# IRQF103C8revC.net
KiCad netlist of a schematic drawn in EAGLE
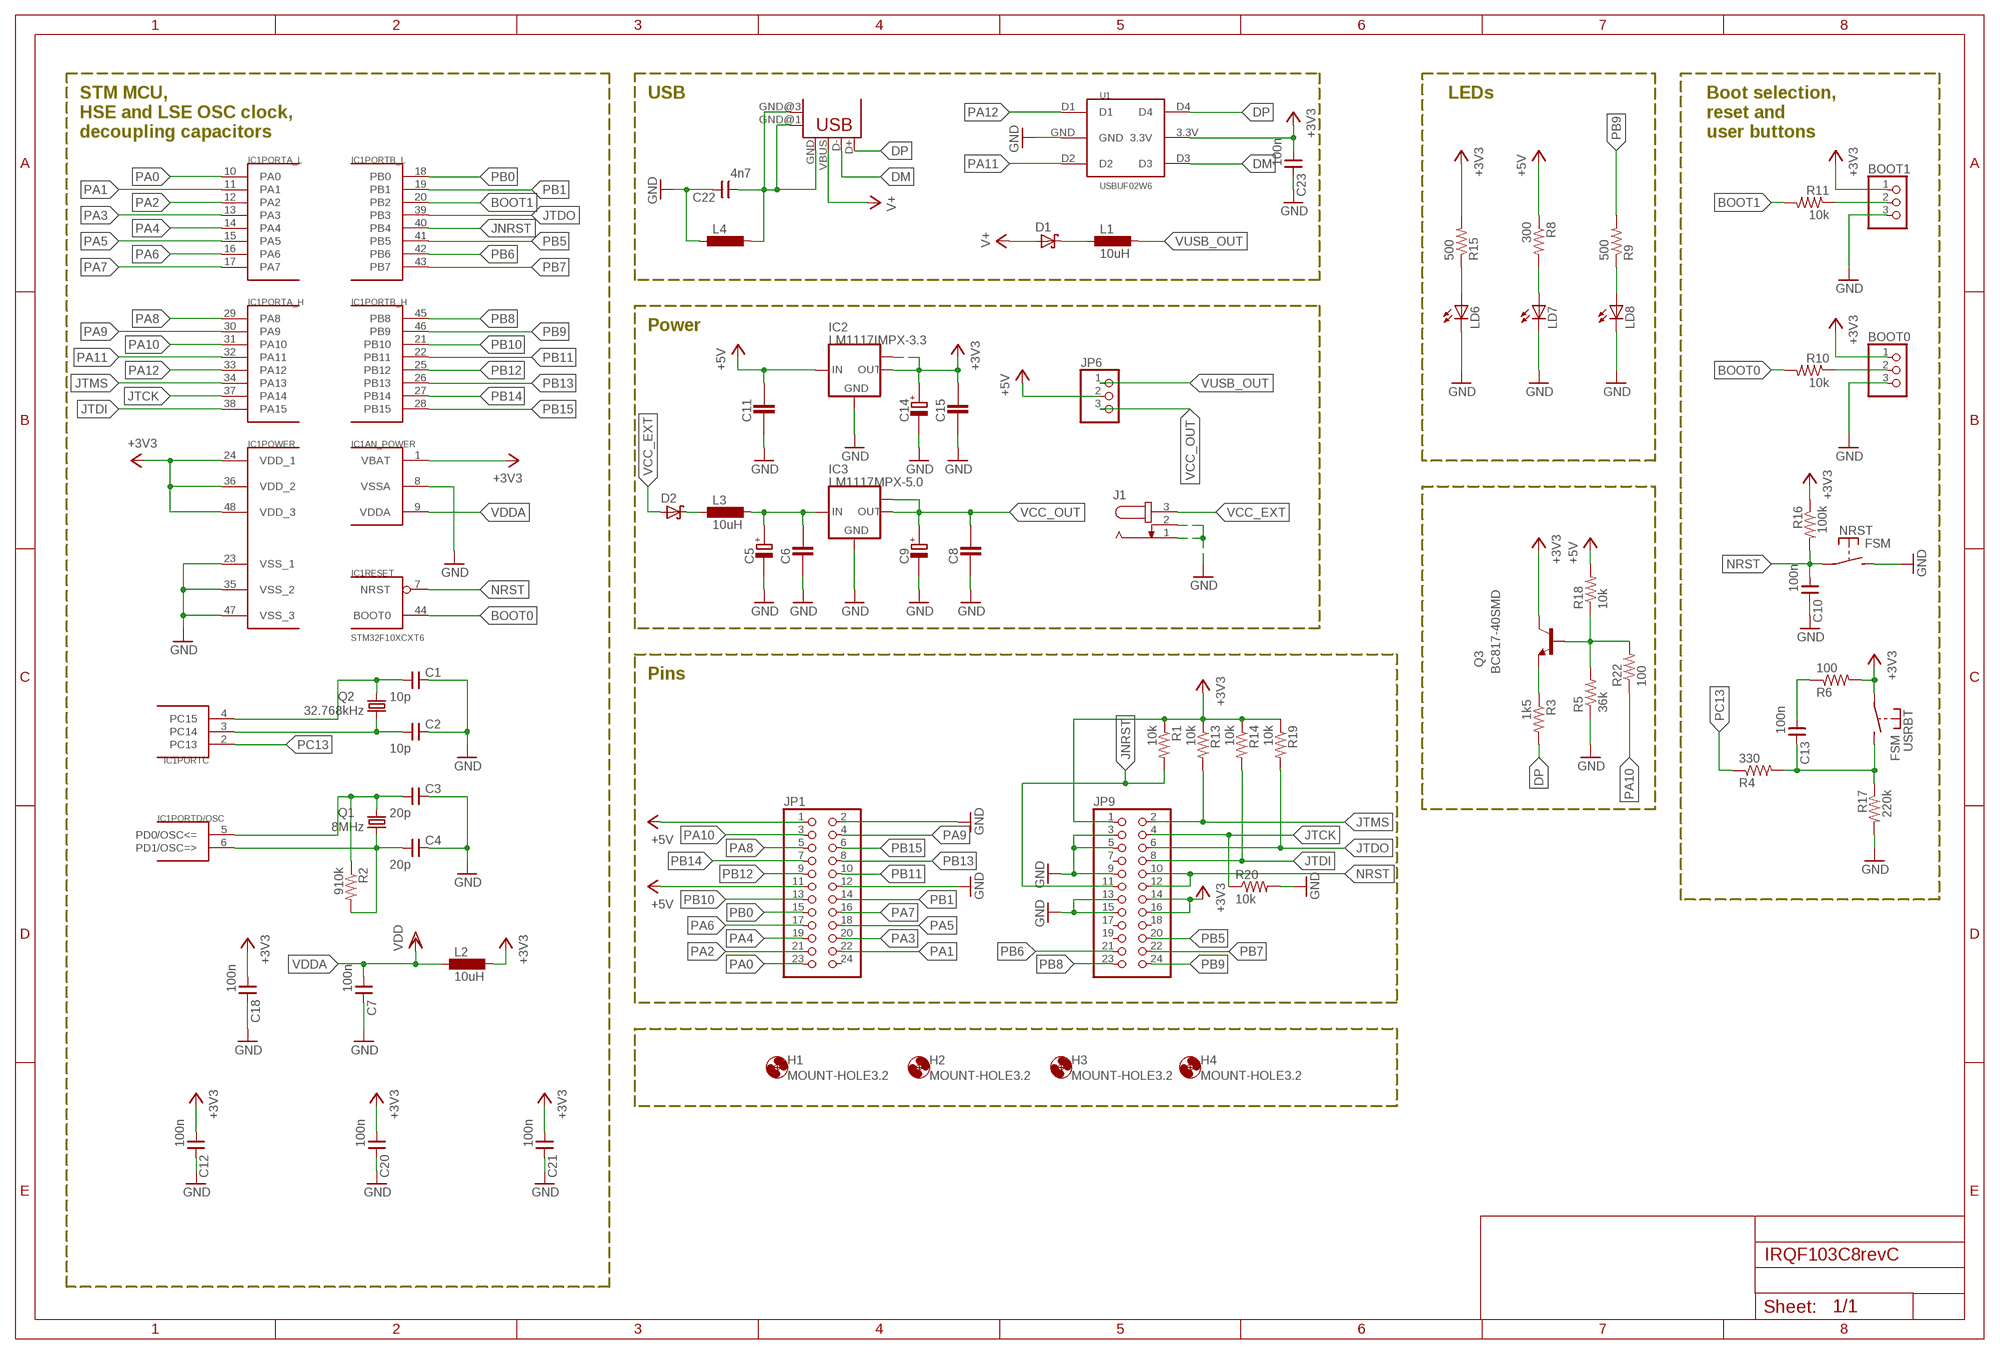
[diagram p0: schematic, sheet 1]

(export (version "E")
  (design (tool "Eeschema 10.0.6"))
  (components
    (comp (ref "BOOT0")
      (value "PINHD-1X3")
      (footprint "eagle-import:1X03")
      (libsource (lib "eagle-import") (part "PINHD-1X3"))
    )
    (comp (ref "BOOT1")
      (value "PINHD-1X3")
      (footprint "eagle-import:1X03")
      (libsource (lib "eagle-import") (part "PINHD-1X3"))
    )
    (comp (ref "C1")
      (value "10p")
      (footprint "eagle-import:0805")
      (libsource (lib "eagle-import") (part "CNP-0805"))
    )
    (comp (ref "C2")
      (value "10p")
      (footprint "eagle-import:0805")
      (libsource (lib "eagle-import") (part "CNP-0805"))
    )
    (comp (ref "C3")
      (value "20p")
      (footprint "eagle-import:0805")
      (libsource (lib "eagle-import") (part "CNP-0805"))
    )
    (comp (ref "C4")
      (value "20p")
      (footprint "eagle-import:0805")
      (libsource (lib "eagle-import") (part "CNP-0805"))
    )
    (comp (ref "C5")
      (value "POLARISED_CASE_B")
      (footprint "eagle-import:CAPAE430X540N")
      (libsource (lib "eagle-import") (part "POLARISED_CASE_B"))
    )
    (comp (ref "C6")
      (value "CAPACITOR_0805")
      (footprint "eagle-import:CAPC2012X145AN")
      (libsource (lib "eagle-import") (part "CAPACITOR_0805"))
    )
    (comp (ref "C7")
      (value "100n")
      (footprint "eagle-import:0805")
      (libsource (lib "eagle-import") (part "CNP-0805"))
    )
    (comp (ref "C8")
      (value "CAPACITOR_0805")
      (footprint "eagle-import:CAPC2012X145AN")
      (libsource (lib "eagle-import") (part "CAPACITOR_0805"))
    )
    (comp (ref "C9")
      (value "POLARISED_CASE_D")
      (footprint "eagle-import:CAPAE660X540N")
      (libsource (lib "eagle-import") (part "POLARISED_CASE_D"))
    )
    (comp (ref "C10")
      (value "100n")
      (footprint "eagle-import:0805")
      (libsource (lib "eagle-import") (part "CNP-0805"))
    )
    (comp (ref "C11")
      (value "CAPACITOR_1206")
      (footprint "eagle-import:CAPC3215X168N")
      (libsource (lib "eagle-import") (part "CAPACITOR_1206"))
    )
    (comp (ref "C12")
      (value "100n")
      (footprint "eagle-import:0805")
      (libsource (lib "eagle-import") (part "CNP-0805"))
    )
    (comp (ref "C13")
      (value "100n")
      (footprint "eagle-import:0805")
      (libsource (lib "eagle-import") (part "CNP-0805"))
    )
    (comp (ref "C14")
      (value "POLARISED_CASE_C")
      (footprint "eagle-import:CAPAE530X540N")
      (libsource (lib "eagle-import") (part "POLARISED_CASE_C"))
    )
    (comp (ref "C15")
      (value "CAPACITOR_0805")
      (footprint "eagle-import:CAPC2012X145AN")
      (libsource (lib "eagle-import") (part "CAPACITOR_0805"))
    )
    (comp (ref "C18")
      (value "100n")
      (footprint "eagle-import:0805")
      (libsource (lib "eagle-import") (part "CNP-0805"))
    )
    (comp (ref "C20")
      (value "100n")
      (footprint "eagle-import:0805")
      (libsource (lib "eagle-import") (part "CNP-0805"))
    )
    (comp (ref "C21")
      (value "100n")
      (footprint "eagle-import:0805")
      (libsource (lib "eagle-import") (part "CNP-0805"))
    )
    (comp (ref "C22")
      (value "4n7")
      (footprint "eagle-import:0805")
      (libsource (lib "eagle-import") (part "CNP-0805"))
    )
    (comp (ref "C23")
      (value "100n")
      (footprint "eagle-import:0805")
      (libsource (lib "eagle-import") (part "CNP-0805"))
    )
    (comp (ref "D1")
      (value "SCHOTTKY_SMA")
      (footprint "eagle-import:DIOM5326X292N")
      (libsource (lib "eagle-import") (part "SCHOTTKY_SMA"))
    )
    (comp (ref "D2")
      (value "SCHOTTKY_SMA")
      (footprint "eagle-import:DIOM5326X292N")
      (libsource (lib "eagle-import") (part "SCHOTTKY_SMA"))
    )
    (comp (ref "H1")
      (value "MOUNT-HOLE3.2")
      (footprint "eagle-import:3,2")
      (libsource (lib "eagle-import") (part "MOUNT-HOLE3.2"))
    )
    (comp (ref "H2")
      (value "MOUNT-HOLE3.2")
      (footprint "eagle-import:3,2")
      (libsource (lib "eagle-import") (part "MOUNT-HOLE3.2"))
    )
    (comp (ref "H3")
      (value "MOUNT-HOLE3.2")
      (footprint "eagle-import:3,2")
      (libsource (lib "eagle-import") (part "MOUNT-HOLE3.2"))
    )
    (comp (ref "H4")
      (value "MOUNT-HOLE3.2")
      (footprint "eagle-import:3,2")
      (libsource (lib "eagle-import") (part "MOUNT-HOLE3.2"))
    )
    (comp (ref "IC1")
      (value "STM32F10XCXT6")
      (footprint "eagle-import:TQFP48")
      (libsource (lib "eagle-import") (part "STM32F10XCXT6"))
    )
    (comp (ref "IC2")
      (value "LM1117IMPX-3.3")
      (footprint "eagle-import:SOT223")
      (libsource (lib "eagle-import") (part "LM1117IMPX-3.3"))
    )
    (comp (ref "IC3")
      (value "LM1117MPX-5.0")
      (footprint "eagle-import:SOT223")
      (libsource (lib "eagle-import") (part "LM1117MPX-5.0"))
    )
    (comp (ref "J1")
      (value "JACK-PLUG1")
      (footprint "eagle-import:SPC4078")
      (libsource (lib "eagle-import") (part "JACK-PLUG1"))
    )
    (comp (ref "JP1")
      (value "PINHD-2X12")
      (footprint "eagle-import:2X12")
      (libsource (lib "eagle-import") (part "PINHD-2X12"))
    )
    (comp (ref "JP6")
      (value "PINHD-1X3")
      (footprint "eagle-import:1X03")
      (libsource (lib "eagle-import") (part "PINHD-1X3"))
    )
    (comp (ref "JP9")
      (value "PINHD-2X12")
      (footprint "eagle-import:2X12")
      (libsource (lib "eagle-import") (part "PINHD-2X12"))
    )
    (comp (ref "L1")
      (value "10uH")
      (footprint "eagle-import:INDC1608X95N")
      (libsource (lib "eagle-import") (part "INDUCTOR_0603"))
    )
    (comp (ref "L2")
      (value "10uH")
      (footprint "eagle-import:INDC1608X95N")
      (libsource (lib "eagle-import") (part "INDUCTOR_0603"))
    )
    (comp (ref "L3")
      (value "10uH")
      (footprint "eagle-import:INDC1608X95N")
      (libsource (lib "eagle-import") (part "INDUCTOR_0603"))
    )
    (comp (ref "L4")
      (value "INDUCTOR_0603")
      (footprint "eagle-import:INDC1608X95N")
      (libsource (lib "eagle-import") (part "INDUCTOR_0603"))
    )
    (comp (ref "LD6")
      (value "LEDCHIPLED_0805")
      (footprint "eagle-import:CHIPLED_0805")
      (libsource (lib "eagle-import") (part "LEDCHIPLED_0805"))
    )
    (comp (ref "LD7")
      (value "LEDCHIPLED_0805")
      (footprint "eagle-import:CHIPLED_0805")
      (libsource (lib "eagle-import") (part "LEDCHIPLED_0805"))
    )
    (comp (ref "LD8")
      (value "LEDCHIPLED_0805")
      (footprint "eagle-import:CHIPLED_0805")
      (libsource (lib "eagle-import") (part "LEDCHIPLED_0805"))
    )
    (comp (ref "NRST")
      (value "FSM")
      (footprint "eagle-import:FSM")
      (libsource (lib "eagle-import") (part "FSM"))
    )
    (comp (ref "Q1")
      (value "8MHz")
      (footprint "eagle-import:HC49_S")
      (libsource (lib "eagle-import") (part "CRYTALHC49S"))
    )
    (comp (ref "Q2")
      (value "32.768kHz")
      (footprint "eagle-import:TC26H")
      (libsource (lib "eagle-import") (part "CRYTALTC26H"))
    )
    (comp (ref "Q3")
      (value "BC817-40SMD")
      (footprint "eagle-import:SOT23-BEC")
      (libsource (lib "eagle-import") (part "BC817SMD-40"))
    )
    (comp (ref "R1")
      (value "10k")
      (footprint "eagle-import:M0805")
      (libsource (lib "eagle-import") (part "R-US_M0805"))
    )
    (comp (ref "R2")
      (value "910k")
      (footprint "eagle-import:M0805")
      (libsource (lib "eagle-import") (part "R-US_M0805"))
    )
    (comp (ref "R3")
      (value "1k5")
      (footprint "eagle-import:M0805")
      (libsource (lib "eagle-import") (part "R-US_M0805"))
    )
    (comp (ref "R4")
      (value "330")
      (footprint "eagle-import:M0805")
      (libsource (lib "eagle-import") (part "R-US_M0805"))
    )
    (comp (ref "R5")
      (value "36k")
      (footprint "eagle-import:M0805")
      (libsource (lib "eagle-import") (part "R-US_M0805"))
    )
    (comp (ref "R6")
      (value "100")
      (footprint "eagle-import:M0805")
      (libsource (lib "eagle-import") (part "R-US_M0805"))
    )
    (comp (ref "R8")
      (value "300")
      (footprint "eagle-import:M0805")
      (libsource (lib "eagle-import") (part "R-US_M0805"))
    )
    (comp (ref "R9")
      (value "500")
      (footprint "eagle-import:M0805")
      (libsource (lib "eagle-import") (part "R-US_M0805"))
    )
    (comp (ref "R10")
      (value "10k")
      (footprint "eagle-import:M0805")
      (libsource (lib "eagle-import") (part "R-US_M0805"))
    )
    (comp (ref "R11")
      (value "10k")
      (footprint "eagle-import:M0805")
      (libsource (lib "eagle-import") (part "R-US_M0805"))
    )
    (comp (ref "R13")
      (value "10k")
      (footprint "eagle-import:M0805")
      (libsource (lib "eagle-import") (part "R-US_M0805"))
    )
    (comp (ref "R14")
      (value "10k")
      (footprint "eagle-import:M0805")
      (libsource (lib "eagle-import") (part "R-US_M0805"))
    )
    (comp (ref "R15")
      (value "500")
      (footprint "eagle-import:M0805")
      (libsource (lib "eagle-import") (part "R-US_M0805"))
    )
    (comp (ref "R16")
      (value "100k")
      (footprint "eagle-import:M0805")
      (libsource (lib "eagle-import") (part "R-US_M0805"))
    )
    (comp (ref "R17")
      (value "220k")
      (footprint "eagle-import:M0805")
      (libsource (lib "eagle-import") (part "R-US_M0805"))
    )
    (comp (ref "R18")
      (value "10k")
      (footprint "eagle-import:M0805")
      (libsource (lib "eagle-import") (part "R-US_M0805"))
    )
    (comp (ref "R19")
      (value "10k")
      (footprint "eagle-import:M0805")
      (libsource (lib "eagle-import") (part "R-US_M0805"))
    )
    (comp (ref "R20")
      (value "10k")
      (footprint "eagle-import:M0805")
      (libsource (lib "eagle-import") (part "R-US_M0805"))
    )
    (comp (ref "R22")
      (value "100")
      (footprint "eagle-import:M0805")
      (libsource (lib "eagle-import") (part "R-US_M0805"))
    )
    (comp (ref "U1")
      (value "USBUF02W6")
      (footprint "eagle-import:SOT23-6L")
      (libsource (lib "eagle-import") (part "USBUF02W6"))
    )
    (comp (ref "USB1")
      (value "USB-MB-S")
      (footprint "eagle-import:USB-MB-S")
      (libsource (lib "eagle-import") (part "USB-MB-S"))
    )
    (comp (ref "USRBT")
      (value "FSM")
      (footprint "eagle-import:FSM")
      (libsource (lib "eagle-import") (part "FSM"))
    )
  )
  (nets
    (net (code "1") (name "+3V3") (class "Default")
      (node (ref "BOOT0") (pin "1") (pinfunction "1_1") (pintype "passive"))
      (node (ref "BOOT1") (pin "1") (pinfunction "1_1") (pintype "passive"))
      (node (ref "C12") (pin "1") (pinfunction "1_1") (pintype "passive"))
      (node (ref "C14") (pin "+") (pinfunction "+_+") (pintype "passive"))
      (node (ref "C15") (pin "2") (pinfunction "2_2") (pintype "passive"))
      (node (ref "C18") (pin "1") (pinfunction "1_1") (pintype "passive"))
      (node (ref "C20") (pin "1") (pinfunction "1_1") (pintype "passive"))
      (node (ref "C21") (pin "1") (pinfunction "1_1") (pintype "passive"))
      (node (ref "C23") (pin "1") (pinfunction "1_1") (pintype "passive"))
      (node (ref "IC1") (pin "1") (pinfunction "VBAT_1") (pintype "power_in"))
      (node (ref "IC1") (pin "24") (pinfunction "VDD_1_24") (pintype "power_in"))
      (node (ref "IC1") (pin "36") (pinfunction "VDD_2_36") (pintype "power_in"))
      (node (ref "IC1") (pin "48") (pinfunction "VDD_3_48") (pintype "power_in"))
      (node (ref "IC2") (pin "2") (pinfunction "OUT_2") (pintype "passive"))
      (node (ref "IC2") (pin "TAB") (pinfunction "OUT1_TAB") (pintype "passive"))
      (node (ref "JP9") (pin "1") (pinfunction "1_1") (pintype "passive"))
      (node (ref "JP9") (pin "14") (pinfunction "14_14") (pintype "passive"))
      (node (ref "JP9") (pin "16") (pinfunction "16_16") (pintype "passive"))
      (node (ref "L2") (pin "2") (pinfunction "2_2") (pintype "passive"))
      (node (ref "Q3") (pin "C") (pinfunction "C_C") (pintype "passive"))
      (node (ref "R1") (pin "1") (pinfunction "1_1") (pintype "passive"))
      (node (ref "R13") (pin "1") (pinfunction "1_1") (pintype "passive"))
      (node (ref "R14") (pin "1") (pinfunction "1_1") (pintype "passive"))
      (node (ref "R15") (pin "2") (pinfunction "2_2") (pintype "passive"))
      (node (ref "R16") (pin "1") (pinfunction "1_1") (pintype "passive"))
      (node (ref "R19") (pin "1") (pinfunction "1_1") (pintype "passive"))
      (node (ref "R6") (pin "2") (pinfunction "2_2") (pintype "passive"))
      (node (ref "U1") (pin "3.3V") (pinfunction "3.3V_3.3V") (pintype "bidirectional"))
      (node (ref "USRBT") (pin "P$1") (pinfunction "P_P$1") (pintype "passive"))
    )
    (net (code "2") (name "+5V") (class "Default")
      (node (ref "C11") (pin "2") (pinfunction "2_2") (pintype "passive"))
      (node (ref "IC2") (pin "3") (pinfunction "IN_3") (pintype "input"))
      (node (ref "JP1") (pin "1") (pinfunction "1_1") (pintype "passive"))
      (node (ref "JP1") (pin "11") (pinfunction "11_11") (pintype "passive"))
      (node (ref "JP6") (pin "2") (pinfunction "2_2") (pintype "passive"))
      (node (ref "R18") (pin "2") (pinfunction "2_2") (pintype "passive"))
      (node (ref "R8") (pin "1") (pinfunction "1_1") (pintype "passive"))
    )
    (net (code "3") (name "BOOT0") (class "Default")
      (node (ref "IC1") (pin "44") (pinfunction "BOOT0_44") (pintype "input"))
      (node (ref "R10") (pin "2") (pinfunction "2_2") (pintype "passive"))
    )
    (net (code "4") (name "BOOT1") (class "Default")
      (node (ref "IC1") (pin "20") (pinfunction "PB2_20") (pintype "bidirectional"))
      (node (ref "R11") (pin "2") (pinfunction "2_2") (pintype "passive"))
    )
    (net (code "5") (name "DM") (class "Default")
      (node (ref "U1") (pin "D3") (pinfunction "D3_D3") (pintype "bidirectional"))
      (node (ref "USB1") (pin "D-") (pinfunction "D-_D-") (pintype "bidirectional"))
    )
    (net (code "6") (name "DP") (class "Default")
      (node (ref "R3") (pin "2") (pinfunction "2_2") (pintype "passive"))
      (node (ref "U1") (pin "D4") (pinfunction "D4_D4") (pintype "bidirectional"))
      (node (ref "USB1") (pin "D+") (pinfunction "D+_D+") (pintype "bidirectional"))
    )
    (net (code "7") (name "GND") (class "Default")
      (node (ref "BOOT0") (pin "3") (pinfunction "3_3") (pintype "passive"))
      (node (ref "BOOT1") (pin "3") (pinfunction "3_3") (pintype "passive"))
      (node (ref "C1") (pin "2") (pinfunction "2_2") (pintype "passive"))
      (node (ref "C10") (pin "2") (pinfunction "2_2") (pintype "passive"))
      (node (ref "C11") (pin "1") (pinfunction "1_1") (pintype "passive"))
      (node (ref "C12") (pin "2") (pinfunction "2_2") (pintype "passive"))
      (node (ref "C14") (pin "-") (pinfunction "-_-") (pintype "passive"))
      (node (ref "C15") (pin "1") (pinfunction "1_1") (pintype "passive"))
      (node (ref "C18") (pin "2") (pinfunction "2_2") (pintype "passive"))
      (node (ref "C2") (pin "2") (pinfunction "2_2") (pintype "passive"))
      (node (ref "C20") (pin "2") (pinfunction "2_2") (pintype "passive"))
      (node (ref "C21") (pin "2") (pinfunction "2_2") (pintype "passive"))
      (node (ref "C22") (pin "2") (pinfunction "2_2") (pintype "passive"))
      (node (ref "C23") (pin "2") (pinfunction "2_2") (pintype "passive"))
      (node (ref "C3") (pin "2") (pinfunction "2_2") (pintype "passive"))
      (node (ref "C4") (pin "2") (pinfunction "2_2") (pintype "passive"))
      (node (ref "C5") (pin "-") (pinfunction "-_-") (pintype "passive"))
      (node (ref "C6") (pin "1") (pinfunction "1_1") (pintype "passive"))
      (node (ref "C7") (pin "2") (pinfunction "2_2") (pintype "passive"))
      (node (ref "C8") (pin "1") (pinfunction "1_1") (pintype "passive"))
      (node (ref "C9") (pin "-") (pinfunction "-_-") (pintype "passive"))
      (node (ref "IC1") (pin "23") (pinfunction "VSS_1_23") (pintype "power_in"))
      (node (ref "IC1") (pin "35") (pinfunction "VSS_2_35") (pintype "power_in"))
      (node (ref "IC1") (pin "47") (pinfunction "VSS_3_47") (pintype "power_in"))
      (node (ref "IC1") (pin "8") (pinfunction "VSSA_8") (pintype "power_in"))
      (node (ref "IC2") (pin "1") (pinfunction "GND_1") (pintype "input"))
      (node (ref "IC3") (pin "1") (pinfunction "GND_1") (pintype "input"))
      (node (ref "J1") (pin "1") (pinfunction "1_1") (pintype "passive"))
      (node (ref "J1") (pin "2") (pinfunction "2_2") (pintype "passive"))
      (node (ref "JP1") (pin "12") (pinfunction "12_12") (pintype "passive"))
      (node (ref "JP1") (pin "2") (pinfunction "2_2") (pintype "passive"))
      (node (ref "JP9") (pin "13") (pinfunction "13_13") (pintype "passive"))
      (node (ref "JP9") (pin "15") (pinfunction "15_15") (pintype "passive"))
      (node (ref "JP9") (pin "3") (pinfunction "3_3") (pintype "passive"))
      (node (ref "JP9") (pin "5") (pinfunction "5_5") (pintype "passive"))
      (node (ref "JP9") (pin "9") (pinfunction "9_9") (pintype "passive"))
      (node (ref "L4") (pin "1") (pinfunction "1_1") (pintype "passive"))
      (node (ref "LD6") (pin "C") (pinfunction "C_C") (pintype "passive"))
      (node (ref "LD7") (pin "C") (pinfunction "C_C") (pintype "passive"))
      (node (ref "LD8") (pin "C") (pinfunction "C_C") (pintype "passive"))
      (node (ref "NRST") (pin "P$2") (pinfunction "S_P$2") (pintype "passive"))
      (node (ref "R17") (pin "2") (pinfunction "2_2") (pintype "passive"))
      (node (ref "R20") (pin "2") (pinfunction "2_2") (pintype "passive"))
      (node (ref "R5") (pin "1") (pinfunction "1_1") (pintype "passive"))
      (node (ref "U1") (pin "GND") (pinfunction "GND_GND") (pintype "bidirectional"))
    )
    (net (code "8") (name "JNRST") (class "Default")
      (node (ref "IC1") (pin "40") (pinfunction "PB4_40") (pintype "bidirectional"))
      (node (ref "JP9") (pin "11") (pinfunction "11_11") (pintype "passive"))
      (node (ref "R1") (pin "2") (pinfunction "2_2") (pintype "passive"))
    )
    (net (code "9") (name "JTCK") (class "Default")
      (node (ref "IC1") (pin "37") (pinfunction "PA14_37") (pintype "bidirectional"))
      (node (ref "JP9") (pin "4") (pinfunction "4_4") (pintype "passive"))
      (node (ref "R20") (pin "1") (pinfunction "1_1") (pintype "passive"))
    )
    (net (code "10") (name "JTDI") (class "Default")
      (node (ref "IC1") (pin "38") (pinfunction "PA15_38") (pintype "bidirectional"))
      (node (ref "JP9") (pin "8") (pinfunction "8_8") (pintype "passive"))
      (node (ref "R14") (pin "2") (pinfunction "2_2") (pintype "passive"))
    )
    (net (code "11") (name "JTDO") (class "Default")
      (node (ref "IC1") (pin "39") (pinfunction "PB3_39") (pintype "bidirectional"))
      (node (ref "JP9") (pin "6") (pinfunction "6_6") (pintype "passive"))
      (node (ref "R19") (pin "2") (pinfunction "2_2") (pintype "passive"))
    )
    (net (code "12") (name "JTMS") (class "Default")
      (node (ref "IC1") (pin "34") (pinfunction "PA13_34") (pintype "bidirectional"))
      (node (ref "JP9") (pin "2") (pinfunction "2_2") (pintype "passive"))
      (node (ref "R13") (pin "2") (pinfunction "2_2") (pintype "passive"))
    )
    (net (code "13") (name "NRST") (class "Default")
      (node (ref "C10") (pin "1") (pinfunction "1_1") (pintype "passive"))
      (node (ref "IC1") (pin "7") (pinfunction "NRST_7") (pintype "input"))
      (node (ref "JP9") (pin "10") (pinfunction "10_10") (pintype "passive"))
      (node (ref "JP9") (pin "12") (pinfunction "12_12") (pintype "passive"))
      (node (ref "NRST") (pin "P$1") (pinfunction "P_P$1") (pintype "passive"))
      (node (ref "R16") (pin "2") (pinfunction "2_2") (pintype "passive"))
    )
    (net (code "14") (name "Net-(BOOT0-Pad2)") (class "Default")
      (node (ref "BOOT0") (pin "2") (pinfunction "2_2") (pintype "passive"))
      (node (ref "R10") (pin "1") (pinfunction "1_1") (pintype "passive"))
    )
    (net (code "15") (name "Net-(BOOT1-Pad2)") (class "Default")
      (node (ref "BOOT1") (pin "2") (pinfunction "2_2") (pintype "passive"))
      (node (ref "R11") (pin "1") (pinfunction "1_1") (pintype "passive"))
    )
    (net (code "16") (name "Net-(C13-Pad1)") (class "Default")
      (node (ref "C13") (pin "1") (pinfunction "1_1") (pintype "passive"))
      (node (ref "R6") (pin "1") (pinfunction "1_1") (pintype "passive"))
    )
    (net (code "17") (name "Net-(C22-Pad1)") (class "Default")
      (node (ref "C22") (pin "1") (pinfunction "1_1") (pintype "passive"))
      (node (ref "L4") (pin "2") (pinfunction "2_2") (pintype "passive"))
      (node (ref "USB1") (pin "GND") (pinfunction "GND_GND") (pintype "bidirectional"))
      (node (ref "USB1") (pin "GND@1") (pinfunction "GND_GND@1") (pintype "bidirectional"))
      (node (ref "USB1") (pin "GND@3") (pinfunction "GND_GND@3") (pintype "bidirectional"))
    )
    (net (code "18") (name "Net-(D1-PadK)") (class "Default")
      (node (ref "D1") (pin "K") (pinfunction "K_K") (pintype "passive"))
      (node (ref "L1") (pin "1") (pinfunction "1_1") (pintype "passive"))
    )
    (net (code "19") (name "Net-(D2-PadK)") (class "Default")
      (node (ref "D2") (pin "K") (pinfunction "K_K") (pintype "passive"))
      (node (ref "L3") (pin "1") (pinfunction "1_1") (pintype "passive"))
    )
    (net (code "20") (name "Net-(IC1F-PC14)") (class "Default")
      (node (ref "C2") (pin "1") (pinfunction "1_1") (pintype "passive"))
      (node (ref "IC1") (pin "3") (pinfunction "PC14_3") (pintype "bidirectional"))
      (node (ref "Q2") (pin "1") (pinfunction "1_1") (pintype "passive"))
    )
    (net (code "21") (name "Net-(IC1F-PC15)") (class "Default")
      (node (ref "C1") (pin "1") (pinfunction "1_1") (pintype "passive"))
      (node (ref "IC1") (pin "4") (pinfunction "PC15_4") (pintype "bidirectional"))
      (node (ref "Q2") (pin "2") (pinfunction "2_2") (pintype "passive"))
    )
    (net (code "22") (name "Net-(IC1G-PD0{slash}OSC<=)") (class "Default")
      (node (ref "C3") (pin "1") (pinfunction "1_1") (pintype "passive"))
      (node (ref "IC1") (pin "5") (pinfunction "PD0/OSC<=_5") (pintype "bidirectional"))
      (node (ref "Q1") (pin "2") (pinfunction "2_2") (pintype "passive"))
      (node (ref "R2") (pin "1") (pinfunction "1_1") (pintype "passive"))
    )
    (net (code "23") (name "Net-(IC1G-PD1{slash}OSC=>)") (class "Default")
      (node (ref "C4") (pin "1") (pinfunction "1_1") (pintype "passive"))
      (node (ref "IC1") (pin "6") (pinfunction "PD1/OSC=>_6") (pintype "bidirectional"))
      (node (ref "Q1") (pin "1") (pinfunction "1_1") (pintype "passive"))
      (node (ref "R2") (pin "2") (pinfunction "2_2") (pintype "passive"))
    )
    (net (code "24") (name "Net-(IC3-IN)") (class "Default")
      (node (ref "C5") (pin "+") (pinfunction "+_+") (pintype "passive"))
      (node (ref "C6") (pin "2") (pinfunction "2_2") (pintype "passive"))
      (node (ref "IC3") (pin "3") (pinfunction "IN_3") (pintype "input"))
      (node (ref "L3") (pin "2") (pinfunction "2_2") (pintype "passive"))
    )
    (net (code "25") (name "Net-(LD6-PadA)") (class "Default")
      (node (ref "LD6") (pin "A") (pinfunction "A_A") (pintype "passive"))
      (node (ref "R15") (pin "1") (pinfunction "1_1") (pintype "passive"))
    )
    (net (code "26") (name "Net-(LD7-PadA)") (class "Default")
      (node (ref "LD7") (pin "A") (pinfunction "A_A") (pintype "passive"))
      (node (ref "R8") (pin "2") (pinfunction "2_2") (pintype "passive"))
    )
    (net (code "27") (name "Net-(LD8-PadA)") (class "Default")
      (node (ref "LD8") (pin "A") (pinfunction "A_A") (pintype "passive"))
      (node (ref "R9") (pin "1") (pinfunction "1_1") (pintype "passive"))
    )
    (net (code "28") (name "Net-(Q3-PadB)") (class "Default")
      (node (ref "Q3") (pin "B") (pinfunction "B_B") (pintype "passive"))
      (node (ref "R18") (pin "1") (pinfunction "1_1") (pintype "passive"))
      (node (ref "R22") (pin "2") (pinfunction "2_2") (pintype "passive"))
      (node (ref "R5") (pin "2") (pinfunction "2_2") (pintype "passive"))
    )
    (net (code "29") (name "Net-(Q3-PadE)") (class "Default")
      (node (ref "Q3") (pin "E") (pinfunction "E_E") (pintype "passive"))
      (node (ref "R3") (pin "1") (pinfunction "1_1") (pintype "passive"))
    )
    (net (code "30") (name "Net-(USRBT-S)") (class "Default")
      (node (ref "C13") (pin "2") (pinfunction "2_2") (pintype "passive"))
      (node (ref "R17") (pin "1") (pinfunction "1_1") (pintype "passive"))
      (node (ref "R4") (pin "2") (pinfunction "2_2") (pintype "passive"))
      (node (ref "USRBT") (pin "P$2") (pinfunction "S_P$2") (pintype "passive"))
    )
    (net (code "31") (name "PA0") (class "Default")
      (node (ref "IC1") (pin "10") (pinfunction "PA0_10") (pintype "bidirectional"))
      (node (ref "JP1") (pin "23") (pinfunction "23_23") (pintype "passive"))
    )
    (net (code "32") (name "PA1") (class "Default")
      (node (ref "IC1") (pin "11") (pinfunction "PA1_11") (pintype "bidirectional"))
      (node (ref "JP1") (pin "22") (pinfunction "22_22") (pintype "passive"))
    )
    (net (code "33") (name "PA2") (class "Default")
      (node (ref "IC1") (pin "12") (pinfunction "PA2_12") (pintype "bidirectional"))
      (node (ref "JP1") (pin "21") (pinfunction "21_21") (pintype "passive"))
    )
    (net (code "34") (name "PA3") (class "Default")
      (node (ref "IC1") (pin "13") (pinfunction "PA3_13") (pintype "bidirectional"))
      (node (ref "JP1") (pin "20") (pinfunction "20_20") (pintype "passive"))
    )
    (net (code "35") (name "PA4") (class "Default")
      (node (ref "IC1") (pin "14") (pinfunction "PA4_14") (pintype "bidirectional"))
      (node (ref "JP1") (pin "19") (pinfunction "19_19") (pintype "passive"))
    )
    (net (code "36") (name "PA5") (class "Default")
      (node (ref "IC1") (pin "15") (pinfunction "PA5_15") (pintype "bidirectional"))
      (node (ref "JP1") (pin "18") (pinfunction "18_18") (pintype "passive"))
    )
    (net (code "37") (name "PA6") (class "Default")
      (node (ref "IC1") (pin "16") (pinfunction "PA6_16") (pintype "bidirectional"))
      (node (ref "JP1") (pin "17") (pinfunction "17_17") (pintype "passive"))
    )
    (net (code "38") (name "PA7") (class "Default")
      (node (ref "IC1") (pin "17") (pinfunction "PA7_17") (pintype "bidirectional"))
      (node (ref "JP1") (pin "16") (pinfunction "16_16") (pintype "passive"))
    )
    (net (code "39") (name "PA8") (class "Default")
      (node (ref "IC1") (pin "29") (pinfunction "PA8_29") (pintype "bidirectional"))
      (node (ref "JP1") (pin "5") (pinfunction "5_5") (pintype "passive"))
    )
    (net (code "40") (name "PA9") (class "Default")
      (node (ref "IC1") (pin "30") (pinfunction "PA9_30") (pintype "bidirectional"))
      (node (ref "JP1") (pin "4") (pinfunction "4_4") (pintype "passive"))
    )
    (net (code "41") (name "PA10") (class "Default")
      (node (ref "IC1") (pin "31") (pinfunction "PA10_31") (pintype "bidirectional"))
      (node (ref "JP1") (pin "3") (pinfunction "3_3") (pintype "passive"))
      (node (ref "R22") (pin "1") (pinfunction "1_1") (pintype "passive"))
    )
    (net (code "42") (name "PA11") (class "Default")
      (node (ref "IC1") (pin "32") (pinfunction "PA11_32") (pintype "bidirectional"))
      (node (ref "U1") (pin "D2") (pinfunction "D2_D2") (pintype "bidirectional"))
    )
    (net (code "43") (name "PA12") (class "Default")
      (node (ref "IC1") (pin "33") (pinfunction "PA12_33") (pintype "bidirectional"))
      (node (ref "U1") (pin "D1") (pinfunction "D1_D1") (pintype "bidirectional"))
    )
    (net (code "44") (name "PB0") (class "Default")
      (node (ref "IC1") (pin "18") (pinfunction "PB0_18") (pintype "bidirectional"))
      (node (ref "JP1") (pin "15") (pinfunction "15_15") (pintype "passive"))
    )
    (net (code "45") (name "PB1") (class "Default")
      (node (ref "IC1") (pin "19") (pinfunction "PB1_19") (pintype "bidirectional"))
      (node (ref "JP1") (pin "14") (pinfunction "14_14") (pintype "passive"))
    )
    (net (code "46") (name "PB5") (class "Default")
      (node (ref "IC1") (pin "41") (pinfunction "PB5_41") (pintype "bidirectional"))
      (node (ref "JP9") (pin "20") (pinfunction "20_20") (pintype "passive"))
    )
    (net (code "47") (name "PB6") (class "Default")
      (node (ref "IC1") (pin "42") (pinfunction "PB6_42") (pintype "bidirectional"))
      (node (ref "JP9") (pin "21") (pinfunction "21_21") (pintype "passive"))
    )
    (net (code "48") (name "PB7") (class "Default")
      (node (ref "IC1") (pin "43") (pinfunction "PB7_43") (pintype "bidirectional"))
      (node (ref "JP9") (pin "22") (pinfunction "22_22") (pintype "passive"))
    )
    (net (code "49") (name "PB8") (class "Default")
      (node (ref "IC1") (pin "45") (pinfunction "PB8_45") (pintype "bidirectional"))
      (node (ref "JP9") (pin "23") (pinfunction "23_23") (pintype "passive"))
    )
    (net (code "50") (name "PB9") (class "Default")
      (node (ref "IC1") (pin "46") (pinfunction "PB9_46") (pintype "bidirectional"))
      (node (ref "JP9") (pin "24") (pinfunction "24_24") (pintype "passive"))
      (node (ref "R9") (pin "2") (pinfunction "2_2") (pintype "passive"))
    )
    (net (code "51") (name "PB10") (class "Default")
      (node (ref "IC1") (pin "21") (pinfunction "PB10_21") (pintype "bidirectional"))
      (node (ref "JP1") (pin "13") (pinfunction "13_13") (pintype "passive"))
    )
    (net (code "52") (name "PB11") (class "Default")
      (node (ref "IC1") (pin "22") (pinfunction "PB11_22") (pintype "bidirectional"))
      (node (ref "JP1") (pin "10") (pinfunction "10_10") (pintype "passive"))
    )
    (net (code "53") (name "PB12") (class "Default")
      (node (ref "IC1") (pin "25") (pinfunction "PB12_25") (pintype "bidirectional"))
      (node (ref "JP1") (pin "9") (pinfunction "9_9") (pintype "passive"))
    )
    (net (code "54") (name "PB13") (class "Default")
      (node (ref "IC1") (pin "26") (pinfunction "PB13_26") (pintype "bidirectional"))
      (node (ref "JP1") (pin "8") (pinfunction "8_8") (pintype "passive"))
    )
    (net (code "55") (name "PB14") (class "Default")
      (node (ref "IC1") (pin "27") (pinfunction "PB14_27") (pintype "bidirectional"))
      (node (ref "JP1") (pin "7") (pinfunction "7_7") (pintype "passive"))
    )
    (net (code "56") (name "PB15") (class "Default")
      (node (ref "IC1") (pin "28") (pinfunction "PB15_28") (pintype "bidirectional"))
      (node (ref "JP1") (pin "6") (pinfunction "6_6") (pintype "passive"))
    )
    (net (code "57") (name "PC13") (class "Default")
      (node (ref "IC1") (pin "2") (pinfunction "PC13_2") (pintype "bidirectional"))
      (node (ref "R4") (pin "1") (pinfunction "1_1") (pintype "passive"))
    )
    (net (code "58") (name "V+") (class "Default")
      (node (ref "D1") (pin "A") (pinfunction "A_A") (pintype "passive"))
      (node (ref "USB1") (pin "VBUS") (pinfunction "VBUS_VBUS") (pintype "bidirectional"))
    )
    (net (code "59") (name "VCC_EXT") (class "Default")
      (node (ref "D2") (pin "A") (pinfunction "A_A") (pintype "passive"))
      (node (ref "J1") (pin "3") (pinfunction "3_3") (pintype "passive"))
    )
    (net (code "60") (name "VCC_OUT") (class "Default")
      (node (ref "C8") (pin "2") (pinfunction "2_2") (pintype "passive"))
      (node (ref "C9") (pin "+") (pinfunction "+_+") (pintype "passive"))
      (node (ref "IC3") (pin "2") (pinfunction "OUT_2") (pintype "passive"))
      (node (ref "IC3") (pin "TAB") (pinfunction "OUT1_TAB") (pintype "passive"))
      (node (ref "JP6") (pin "3") (pinfunction "3_3") (pintype "passive"))
    )
    (net (code "61") (name "VDDA") (class "Default")
      (node (ref "C7") (pin "1") (pinfunction "1_1") (pintype "passive"))
      (node (ref "IC1") (pin "9") (pinfunction "VDDA_9") (pintype "power_in"))
      (node (ref "L2") (pin "1") (pinfunction "1_1") (pintype "passive"))
    )
    (net (code "62") (name "VUSB_OUT") (class "Default")
      (node (ref "JP6") (pin "1") (pinfunction "1_1") (pintype "passive"))
      (node (ref "L1") (pin "2") (pinfunction "2_2") (pintype "passive"))
    )
    (net (code "63") (name "unconnected-(JP1-Pad24)") (class "Default")
      (node (ref "JP1") (pin "24") (pinfunction "24_24") (pintype "passive"))
    )
    (net (code "64") (name "unconnected-(JP9-Pad7)") (class "Default")
      (node (ref "JP9") (pin "7") (pinfunction "7_7") (pintype "passive"))
    )
    (net (code "65") (name "unconnected-(JP9-Pad17)") (class "Default")
      (node (ref "JP9") (pin "17") (pinfunction "17_17") (pintype "passive"))
    )
    (net (code "66") (name "unconnected-(JP9-Pad18)") (class "Default")
      (node (ref "JP9") (pin "18") (pinfunction "18_18") (pintype "passive"))
    )
    (net (code "67") (name "unconnected-(JP9-Pad19)") (class "Default")
      (node (ref "JP9") (pin "19") (pinfunction "19_19") (pintype "passive"))
    )
  )
)
